# Adafruit_FONA_SIM5320_3G_Breakout.net
KiCad netlist of a schematic drawn in EAGLE
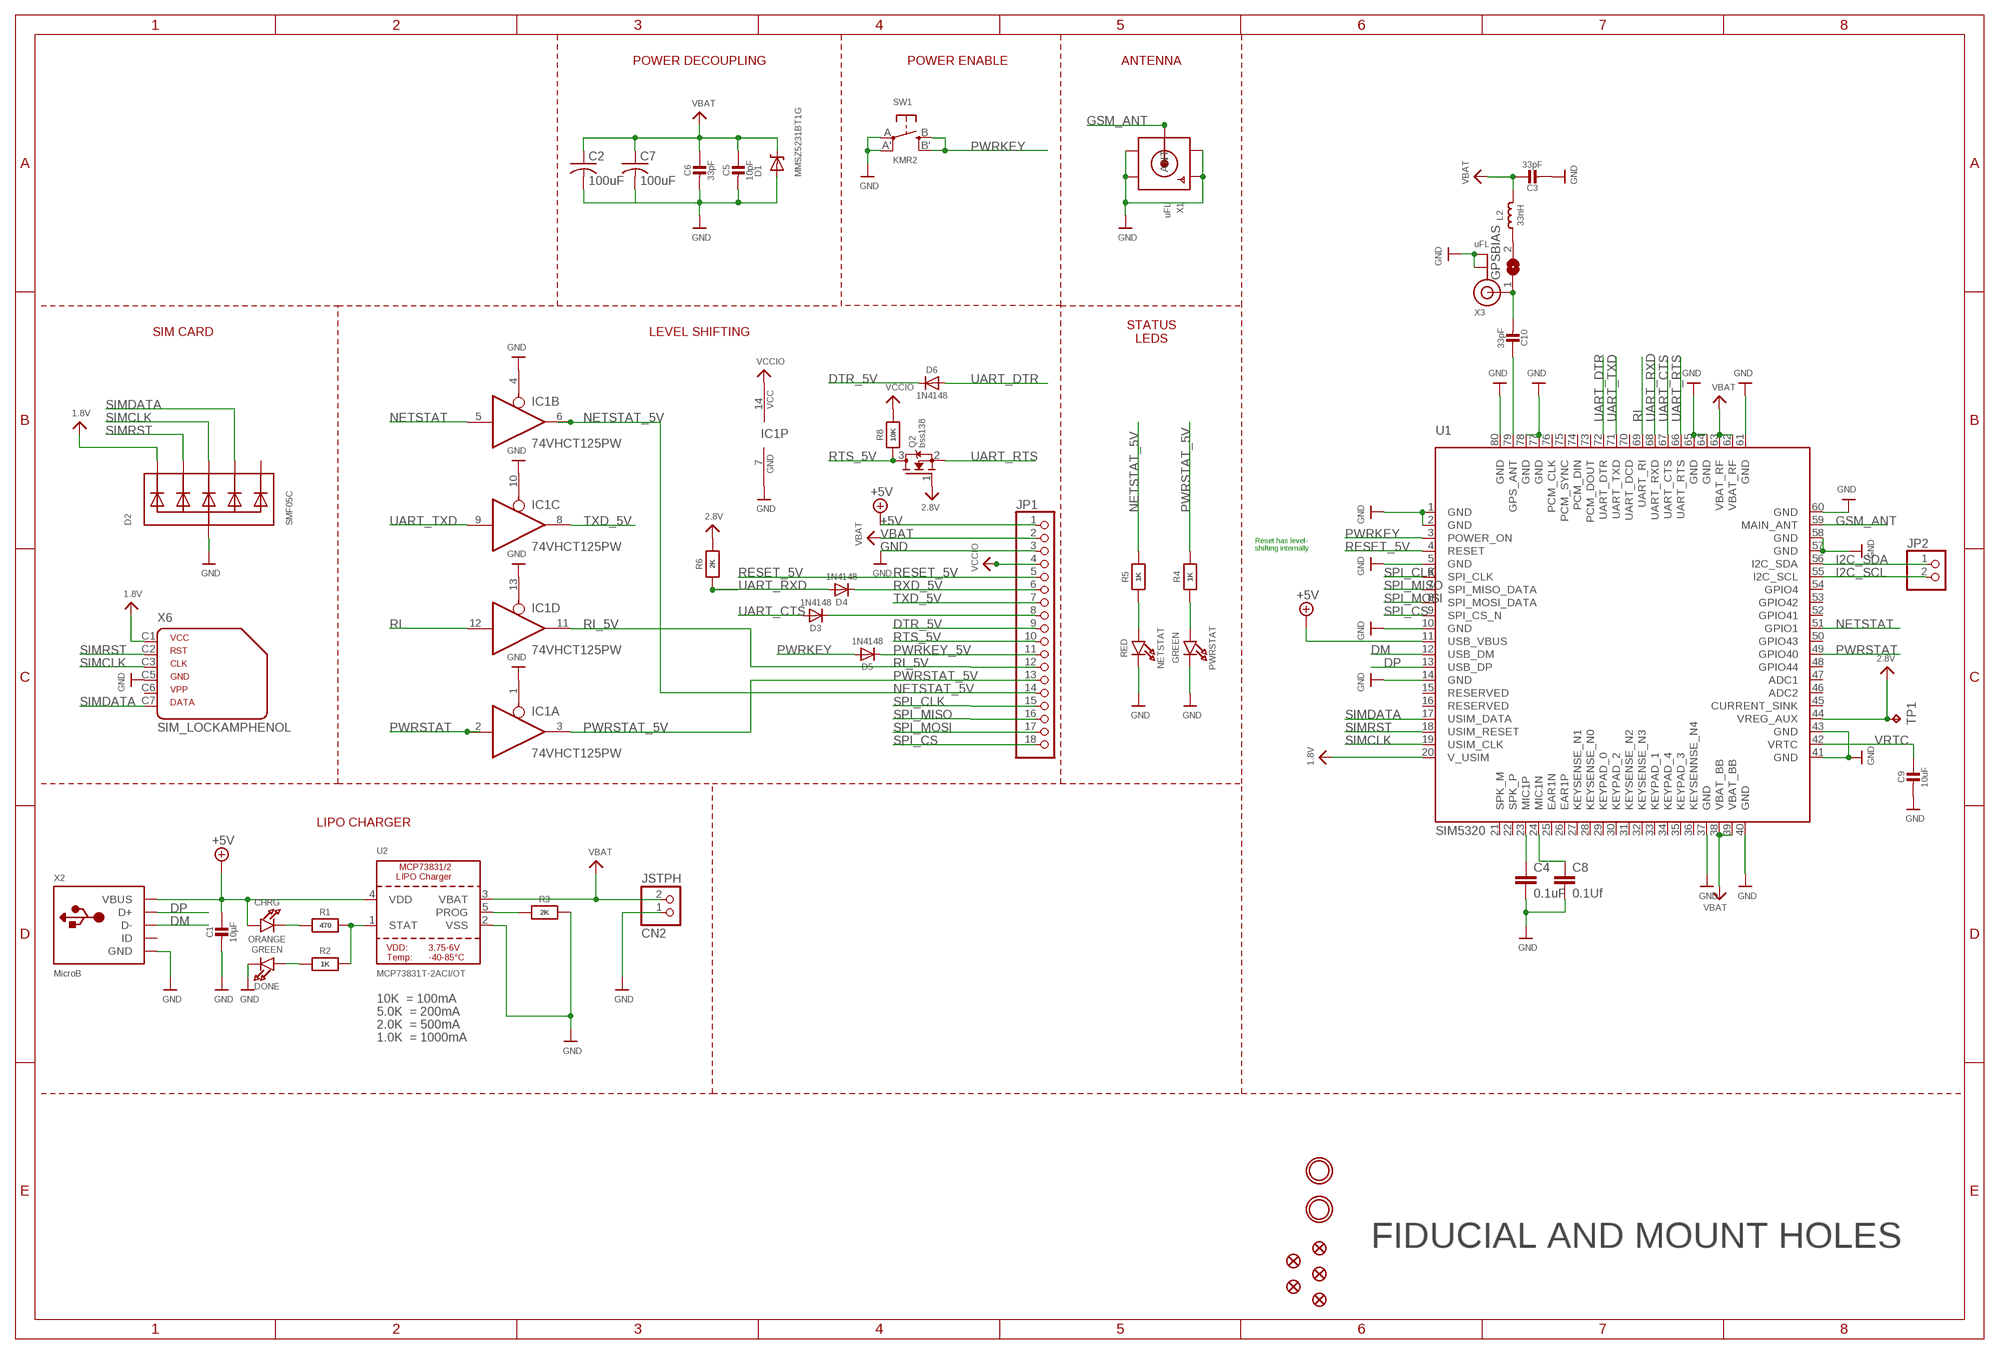
[diagram p0: schematic, sheet 1]

(export (version "E")
  (design (tool "Eeschema 10.0.6"))
  (components
    (comp (ref "C1")
      (value "10µF")
      (footprint "eagle-import:0805-NO")
      (libsource (lib "eagle-import") (part "CAP_CERAMIC0805-NOOUTLINE"))
    )
    (comp (ref "C2")
      (value "100uF")
      (footprint "eagle-import:C1210")
      (libsource (lib "eagle-import") (part "C-USC1210"))
    )
    (comp (ref "C3")
      (value "33pF")
      (footprint "eagle-import:0805-NO")
      (libsource (lib "eagle-import") (part "CAP_CERAMIC0805-NOOUTLINE"))
    )
    (comp (ref "C4")
      (value "0.1uF")
      (footprint "eagle-import:C1210")
      (libsource (lib "eagle-import") (part "C-EUC1210"))
    )
    (comp (ref "C5")
      (value "10pF")
      (footprint "eagle-import:0805-NO")
      (libsource (lib "eagle-import") (part "CAP_CERAMIC0805-NOOUTLINE"))
    )
    (comp (ref "C6")
      (value "33pF")
      (footprint "eagle-import:0805-NO")
      (libsource (lib "eagle-import") (part "CAP_CERAMIC0805-NOOUTLINE"))
    )
    (comp (ref "C7")
      (value "100uF")
      (footprint "eagle-import:C1210")
      (libsource (lib "eagle-import") (part "C-USC1210"))
    )
    (comp (ref "C8")
      (value "0.1Uf")
      (footprint "eagle-import:C1210")
      (libsource (lib "eagle-import") (part "C-EUC1210"))
    )
    (comp (ref "C9")
      (value "10uF")
      (footprint "eagle-import:0805-NO")
      (libsource (lib "eagle-import") (part "CAP_CERAMIC0805-NOOUTLINE"))
    )
    (comp (ref "C10")
      (value "33pF")
      (footprint "eagle-import:0805-NO")
      (libsource (lib "eagle-import") (part "CAP_CERAMIC0805-NOOUTLINE"))
    )
    (comp (ref "CHRG")
      (value "ORANGE")
      (footprint "eagle-import:CHIPLED_0805_NOOUTLINE")
      (libsource (lib "eagle-import") (part "LED0805_NOOUTLINE"))
    )
    (comp (ref "CN2")
      (value "JSTPH")
      (footprint "eagle-import:JSTPH2")
      (libsource (lib "eagle-import") (part "JST_2PIN"))
    )
    (comp (ref "D1")
      (value "MMSZ5231BT1G")
      (footprint "eagle-import:SOD-123")
      (libsource (lib "eagle-import") (part "DIODE-ZENERSOD123"))
    )
    (comp (ref "D2")
      (value "SMF05C")
      (footprint "eagle-import:SOT363")
      (libsource (lib "eagle-import") (part "TVSARRAY_5LANE"))
    )
    (comp (ref "D3")
      (value "1N4148")
      (footprint "eagle-import:SOD-323")
      (libsource (lib "eagle-import") (part "DIODESOD-323"))
    )
    (comp (ref "D4")
      (value "1N4148")
      (footprint "eagle-import:SOD-323")
      (libsource (lib "eagle-import") (part "DIODESOD-323"))
    )
    (comp (ref "D5")
      (value "1N4148")
      (footprint "eagle-import:SOD-323")
      (libsource (lib "eagle-import") (part "DIODESOD-323"))
    )
    (comp (ref "D6")
      (value "1N4148")
      (footprint "eagle-import:SOD-323")
      (libsource (lib "eagle-import") (part "DIODESOD-323"))
    )
    (comp (ref "DONE")
      (value "GREEN")
      (footprint "eagle-import:CHIPLED_0805_NOOUTLINE")
      (libsource (lib "eagle-import") (part "LED0805_NOOUTLINE"))
    )
    (comp (ref "FID1")
      (value "FIDUCIAL\"\"")
      (footprint "eagle-import:FIDUCIAL_1MM")
      (libsource (lib "eagle-import") (part "FIDUCIAL{dblquote}{dblquote}"))
    )
    (comp (ref "FID2")
      (value "FIDUCIAL\"\"")
      (footprint "eagle-import:FIDUCIAL_1MM")
      (libsource (lib "eagle-import") (part "FIDUCIAL{dblquote}{dblquote}"))
    )
    (comp (ref "FID3")
      (value "FIDUCIAL\"\"")
      (footprint "eagle-import:FIDUCIAL_1MM")
      (libsource (lib "eagle-import") (part "FIDUCIAL{dblquote}{dblquote}"))
    )
    (comp (ref "FID4")
      (value "FIDUCIAL\"\"")
      (footprint "eagle-import:FIDUCIAL_1MM")
      (libsource (lib "eagle-import") (part "FIDUCIAL{dblquote}{dblquote}"))
    )
    (comp (ref "FID5")
      (value "FIDUCIAL\"\"")
      (footprint "eagle-import:FIDUCIAL_1MM")
      (libsource (lib "eagle-import") (part "FIDUCIAL{dblquote}{dblquote}"))
    )
    (comp (ref "GPSBIAS")
      (value "SOLDERJUMPER")
      (footprint "eagle-import:SOLDERJUMPER_ARROW_NOPASTE")
      (libsource (lib "eagle-import") (part "SOLDERJUMPER"))
    )
    (comp (ref "IC1")
      (value "74VHCT125PW")
      (footprint "eagle-import:TSSOP14")
      (libsource (lib "eagle-import") (part "74125PWABT"))
    )
    (comp (ref "JP1")
      (value "HEADER-1X18")
      (footprint "eagle-import:1X18_ROUND70")
      (libsource (lib "eagle-import") (part "HEADER-1X18"))
    )
    (comp (ref "JP2")
      (value "HEADER-1X2ROUND")
      (footprint "eagle-import:1X02_ROUND")
      (libsource (lib "eagle-import") (part "HEADER-1X2ROUND"))
    )
    (comp (ref "L2")
      (value "33nH")
      (footprint "eagle-import:_0805MP")
      (libsource (lib "eagle-import") (part "INDUCTOR_0805MP"))
    )
    (comp (ref "NETSTAT")
      (value "RED")
      (footprint "eagle-import:CHIPLED_0805_NOOUTLINE")
      (libsource (lib "eagle-import") (part "LED0805_NOOUTLINE"))
    )
    (comp (ref "PWRSTAT")
      (value "GREEN")
      (footprint "eagle-import:CHIPLED_0805_NOOUTLINE")
      (libsource (lib "eagle-import") (part "LED0805_NOOUTLINE"))
    )
    (comp (ref "Q2")
      (value "bss138")
      (footprint "eagle-import:SOT23-WIDE")
      (libsource (lib "eagle-import") (part "MOSFET-NWIDE"))
    )
    (comp (ref "R1")
      (value "470")
      (footprint "eagle-import:0805-NO")
      (libsource (lib "eagle-import") (part "RESISTOR0805_NOOUTLINE"))
    )
    (comp (ref "R2")
      (value "1K")
      (footprint "eagle-import:0805-NO")
      (libsource (lib "eagle-import") (part "RESISTOR0805_NOOUTLINE"))
    )
    (comp (ref "R3")
      (value "2K")
      (footprint "eagle-import:0805-NO")
      (libsource (lib "eagle-import") (part "RESISTOR0805_NOOUTLINE"))
    )
    (comp (ref "R4")
      (value "1K")
      (footprint "eagle-import:0805-NO")
      (libsource (lib "eagle-import") (part "RESISTOR0805_NOOUTLINE"))
    )
    (comp (ref "R5")
      (value "1K")
      (footprint "eagle-import:0805-NO")
      (libsource (lib "eagle-import") (part "RESISTOR0805_NOOUTLINE"))
    )
    (comp (ref "R6")
      (value "2K")
      (footprint "eagle-import:0805-NO")
      (libsource (lib "eagle-import") (part "RESISTOR0805_NOOUTLINE"))
    )
    (comp (ref "R8")
      (value "10K")
      (footprint "eagle-import:0805-NO")
      (libsource (lib "eagle-import") (part "RESISTOR0805_NOOUTLINE"))
    )
    (comp (ref "SW1")
      (value "KMR2")
      (footprint "eagle-import:BTN_KMR2_4.6X2.8")
      (libsource (lib "eagle-import") (part "SWITCH_TACT_SMT4.6X2.8"))
    )
    (comp (ref "TP1")
      (value "TPTP11R")
      (footprint "eagle-import:TP11R")
      (libsource (lib "eagle-import") (part "TPTP11R"))
    )
    (comp (ref "U$33")
      (value "MOUNTINGHOLE2.5")
      (footprint "eagle-import:MOUNTINGHOLE_2.5_PLATED")
      (libsource (lib "eagle-import") (part "MOUNTINGHOLE2.5"))
    )
    (comp (ref "U$34")
      (value "MOUNTINGHOLE2.5")
      (footprint "eagle-import:MOUNTINGHOLE_2.5_PLATED")
      (libsource (lib "eagle-import") (part "MOUNTINGHOLE2.5"))
    )
    (comp (ref "U1")
      (value "SIM5320")
      (footprint "eagle-import:SIM5320")
      (libsource (lib "eagle-import") (part "GSM_SIM5320_LITERAL"))
    )
    (comp (ref "U2")
      (value "MCP73831T-2ACI/OT")
      (footprint "eagle-import:SOT23-5")
      (libsource (lib "eagle-import") (part "MCP73831/2"))
    )
    (comp (ref "X1")
      (value "uFL")
      (footprint "eagle-import:SMA_EDGELAUNCH_UFL")
      (libsource (lib "eagle-import") (part "SMACONNECTOR_EDGE_UFL"))
    )
    (comp (ref "X2")
      (value "MicroB")
      (footprint "eagle-import:4UCONN_20329")
      (libsource (lib "eagle-import") (part "USBMICRO_20329"))
    )
    (comp (ref "X3")
      (value "uFL")
      (footprint "eagle-import:U.FL")
      (libsource (lib "eagle-import") (part "ANTENNA_U.FL"))
    )
    (comp (ref "X6")
      (value "SIM_LOCKAMPHENOL")
      (footprint "eagle-import:C707_10M006_512_2")
      (libsource (lib "eagle-import") (part "SIM_LOCKAMPHENOL"))
    )
  )
  (nets
    (net (code "1") (name "+5V") (class "Default")
      (node (ref "C1") (pin "1") (pinfunction "1_1") (pintype "passive"))
      (node (ref "CHRG") (pin "A") (pinfunction "A_A") (pintype "passive"))
      (node (ref "JP1") (pin "1") (pinfunction "1_1") (pintype "passive"))
      (node (ref "U1") (pin "11") (pinfunction "USB_VBUS_11") (pintype "bidirectional"))
      (node (ref "U2") (pin "4") (pinfunction "VDD_4") (pintype "power_in"))
      (node (ref "X2") (pin "VBUS") (pinfunction "VBUS_VBUS") (pintype "power_in"))
    )
    (net (code "2") (name "/DM") (class "Default")
      (node (ref "U1") (pin "12") (pinfunction "USB_DM_12") (pintype "bidirectional"))
      (node (ref "X2") (pin "D-") (pinfunction "D-_D-") (pintype "bidirectional"))
    )
    (net (code "3") (name "/DP") (class "Default")
      (node (ref "U1") (pin "13") (pinfunction "USB_DP_13") (pintype "bidirectional"))
      (node (ref "X2") (pin "D+") (pinfunction "D+_D+") (pintype "bidirectional"))
    )
    (net (code "4") (name "/DTR_5V") (class "Default")
      (node (ref "D6") (pin "C") (pinfunction "C_C") (pintype "passive"))
      (node (ref "JP1") (pin "9") (pinfunction "9_9") (pintype "passive"))
    )
    (net (code "5") (name "/GSM_ANT") (class "Default")
      (node (ref "U1") (pin "59") (pinfunction "MAIN_ANT_59") (pintype "bidirectional"))
      (node (ref "X1") (pin "P") (pinfunction "ANT_P") (pintype "bidirectional"))
    )
    (net (code "6") (name "/I2C_SCL") (class "Default")
      (node (ref "JP2") (pin "2") (pinfunction "2_2") (pintype "passive"))
      (node (ref "U1") (pin "55") (pinfunction "I2C_SCL_55") (pintype "bidirectional"))
    )
    (net (code "7") (name "/I2C_SDA") (class "Default")
      (node (ref "JP2") (pin "1") (pinfunction "1_1") (pintype "passive"))
      (node (ref "U1") (pin "56") (pinfunction "I2C_SDA_56") (pintype "bidirectional"))
    )
    (net (code "8") (name "/NETSTAT") (class "Default")
      (node (ref "IC1") (pin "5") (pinfunction "I_5") (pintype "input"))
      (node (ref "U1") (pin "51") (pinfunction "GPIO1_51") (pintype "bidirectional"))
    )
    (net (code "9") (name "/NETSTAT_5V") (class "Default")
      (node (ref "IC1") (pin "6") (pinfunction "O_6") (pintype "tri_state"))
      (node (ref "JP1") (pin "14") (pinfunction "14_14") (pintype "passive"))
      (node (ref "R5") (pin "2") (pinfunction "2_2") (pintype "passive"))
    )
    (net (code "10") (name "/PWRKEY") (class "Default")
      (node (ref "D5") (pin "A") (pinfunction "A_A") (pintype "passive"))
      (node (ref "SW1") (pin "B") (pinfunction "S_B") (pintype "passive"))
      (node (ref "SW1") (pin "B'") (pinfunction "S1_B'") (pintype "passive"))
      (node (ref "U1") (pin "3") (pinfunction "POWER_ON_3") (pintype "bidirectional"))
    )
    (net (code "11") (name "/PWRKEY_5V") (class "Default")
      (node (ref "D5") (pin "C") (pinfunction "C_C") (pintype "passive"))
      (node (ref "JP1") (pin "11") (pinfunction "11_11") (pintype "passive"))
    )
    (net (code "12") (name "/PWRSTAT") (class "Default")
      (node (ref "IC1") (pin "2") (pinfunction "I_2") (pintype "input"))
      (node (ref "U1") (pin "49") (pinfunction "GPIO40_49") (pintype "bidirectional"))
    )
    (net (code "13") (name "/PWRSTAT_5V") (class "Default")
      (node (ref "IC1") (pin "3") (pinfunction "O_3") (pintype "tri_state"))
      (node (ref "JP1") (pin "13") (pinfunction "13_13") (pintype "passive"))
      (node (ref "R4") (pin "2") (pinfunction "2_2") (pintype "passive"))
    )
    (net (code "14") (name "/RESET_5V") (class "Default")
      (node (ref "JP1") (pin "5") (pinfunction "5_5") (pintype "passive"))
      (node (ref "U1") (pin "4") (pinfunction "RESET_4") (pintype "bidirectional"))
    )
    (net (code "15") (name "/RI") (class "Default")
      (node (ref "IC1") (pin "12") (pinfunction "I_12") (pintype "input"))
      (node (ref "U1") (pin "69") (pinfunction "UART_RI_69") (pintype "bidirectional"))
    )
    (net (code "16") (name "/RI_5V") (class "Default")
      (node (ref "IC1") (pin "11") (pinfunction "O_11") (pintype "tri_state"))
      (node (ref "JP1") (pin "12") (pinfunction "12_12") (pintype "passive"))
    )
    (net (code "17") (name "/RTS_5V") (class "Default")
      (node (ref "JP1") (pin "10") (pinfunction "10_10") (pintype "passive"))
      (node (ref "Q2") (pin "3") (pinfunction "D_3") (pintype "bidirectional"))
      (node (ref "R8") (pin "1") (pinfunction "1_1") (pintype "passive"))
    )
    (net (code "18") (name "/RXD_5V") (class "Default")
      (node (ref "D4") (pin "C") (pinfunction "C_C") (pintype "passive"))
      (node (ref "JP1") (pin "6") (pinfunction "6_6") (pintype "passive"))
    )
    (net (code "19") (name "/SIMCLK") (class "Default")
      (node (ref "D2") (pin "4") (pinfunction "C3_4") (pintype "passive"))
      (node (ref "U1") (pin "19") (pinfunction "USIM_CLK_19") (pintype "bidirectional"))
      (node (ref "X6") (pin "C3") (pinfunction "3_C3") (pintype "passive"))
    )
    (net (code "20") (name "/SIMDATA") (class "Default")
      (node (ref "D2") (pin "5") (pinfunction "C4_5") (pintype "passive"))
      (node (ref "U1") (pin "17") (pinfunction "USIM_DATA_17") (pintype "bidirectional"))
      (node (ref "X6") (pin "C7") (pinfunction "6_C7") (pintype "passive"))
    )
    (net (code "21") (name "/SIMRST") (class "Default")
      (node (ref "D2") (pin "3") (pinfunction "C2_3") (pintype "passive"))
      (node (ref "U1") (pin "18") (pinfunction "USIM_RESET_18") (pintype "bidirectional"))
      (node (ref "X6") (pin "C2") (pinfunction "2_C2") (pintype "passive"))
    )
    (net (code "22") (name "/SPI_CLK") (class "Default")
      (node (ref "JP1") (pin "15") (pinfunction "15_15") (pintype "passive"))
      (node (ref "U1") (pin "6") (pinfunction "SPI_CLK_6") (pintype "bidirectional"))
    )
    (net (code "23") (name "/SPI_CS") (class "Default")
      (node (ref "JP1") (pin "18") (pinfunction "18_18") (pintype "passive"))
      (node (ref "U1") (pin "9") (pinfunction "SPI_CS_N_9") (pintype "bidirectional"))
    )
    (net (code "24") (name "/SPI_MISO") (class "Default")
      (node (ref "JP1") (pin "16") (pinfunction "16_16") (pintype "passive"))
      (node (ref "U1") (pin "7") (pinfunction "SPI_MISO_DATA_7") (pintype "bidirectional"))
    )
    (net (code "25") (name "/SPI_MOSI") (class "Default")
      (node (ref "JP1") (pin "17") (pinfunction "17_17") (pintype "passive"))
      (node (ref "U1") (pin "8") (pinfunction "SPI_MOSI_DATA_8") (pintype "bidirectional"))
    )
    (net (code "26") (name "/TXD_5V") (class "Default")
      (node (ref "IC1") (pin "8") (pinfunction "O_8") (pintype "tri_state"))
      (node (ref "JP1") (pin "7") (pinfunction "7_7") (pintype "passive"))
    )
    (net (code "27") (name "/UART_CTS") (class "Default")
      (node (ref "D3") (pin "A") (pinfunction "A_A") (pintype "passive"))
      (node (ref "U1") (pin "67") (pinfunction "UART_CTS_67") (pintype "bidirectional"))
    )
    (net (code "28") (name "/UART_DTR") (class "Default")
      (node (ref "D6") (pin "A") (pinfunction "A_A") (pintype "passive"))
      (node (ref "U1") (pin "72") (pinfunction "UART_DTR_72") (pintype "bidirectional"))
    )
    (net (code "29") (name "/UART_RTS") (class "Default")
      (node (ref "Q2") (pin "2") (pinfunction "S_2") (pintype "bidirectional"))
      (node (ref "U1") (pin "66") (pinfunction "UART_RTS_66") (pintype "bidirectional"))
    )
    (net (code "30") (name "/UART_RXD") (class "Default")
      (node (ref "D4") (pin "A") (pinfunction "A_A") (pintype "passive"))
      (node (ref "R6") (pin "1") (pinfunction "1_1") (pintype "passive"))
      (node (ref "U1") (pin "68") (pinfunction "UART_RXD_68") (pintype "bidirectional"))
    )
    (net (code "31") (name "/UART_TXD") (class "Default")
      (node (ref "IC1") (pin "9") (pinfunction "I_9") (pintype "input"))
      (node (ref "U1") (pin "71") (pinfunction "UART_TXD_71") (pintype "bidirectional"))
    )
    (net (code "32") (name "/VRTC") (class "Default")
      (node (ref "C9") (pin "1") (pinfunction "1_1") (pintype "passive"))
      (node (ref "U1") (pin "42") (pinfunction "VRTC_42") (pintype "bidirectional"))
    )
    (net (code "33") (name "1.8V") (class "Default")
      (node (ref "D2") (pin "1") (pinfunction "C1_1") (pintype "passive"))
      (node (ref "U1") (pin "20") (pinfunction "V_USIM_20") (pintype "bidirectional"))
      (node (ref "X6") (pin "C1") (pinfunction "1_C1") (pintype "passive"))
    )
    (net (code "34") (name "2.8V") (class "Default")
      (node (ref "Q2") (pin "1") (pinfunction "G_1") (pintype "bidirectional"))
      (node (ref "R6") (pin "2") (pinfunction "2_2") (pintype "passive"))
      (node (ref "TP1") (pin "TP") (pinfunction "TP_TP") (pintype "input"))
      (node (ref "U1") (pin "44") (pinfunction "VREG_AUX_44") (pintype "bidirectional"))
    )
    (net (code "35") (name "GND") (class "Default")
      (node (ref "C1") (pin "2") (pinfunction "2_2") (pintype "passive"))
      (node (ref "C2") (pin "2") (pinfunction "2_2") (pintype "passive"))
      (node (ref "C3") (pin "2") (pinfunction "2_2") (pintype "passive"))
      (node (ref "C4") (pin "2") (pinfunction "2_2") (pintype "passive"))
      (node (ref "C5") (pin "2") (pinfunction "2_2") (pintype "passive"))
      (node (ref "C6") (pin "2") (pinfunction "2_2") (pintype "passive"))
      (node (ref "C7") (pin "2") (pinfunction "2_2") (pintype "passive"))
      (node (ref "C8") (pin "2") (pinfunction "2_2") (pintype "passive"))
      (node (ref "C9") (pin "2") (pinfunction "2_2") (pintype "passive"))
      (node (ref "CN2") (pin "1") (pinfunction "1_1") (pintype "passive"))
      (node (ref "D1") (pin "A") (pinfunction "A_A") (pintype "passive"))
      (node (ref "D2") (pin "2") (pinfunction "A_2") (pintype "passive"))
      (node (ref "DONE") (pin "C") (pinfunction "C_C") (pintype "passive"))
      (node (ref "IC1") (pin "1") (pinfunction "OE_1") (pintype "input"))
      (node (ref "IC1") (pin "10") (pinfunction "OE_10") (pintype "input"))
      (node (ref "IC1") (pin "13") (pinfunction "OE_13") (pintype "input"))
      (node (ref "IC1") (pin "4") (pinfunction "OE_4") (pintype "input"))
      (node (ref "IC1") (pin "7") (pinfunction "GND_7") (pintype "power_in"))
      (node (ref "JP1") (pin "3") (pinfunction "3_3") (pintype "passive"))
      (node (ref "NETSTAT") (pin "C") (pinfunction "C_C") (pintype "passive"))
      (node (ref "PWRSTAT") (pin "C") (pinfunction "C_C") (pintype "passive"))
      (node (ref "R3") (pin "2") (pinfunction "2_2") (pintype "passive"))
      (node (ref "SW1") (pin "A") (pinfunction "P_A") (pintype "passive"))
      (node (ref "SW1") (pin "A'") (pinfunction "P1_A'") (pintype "passive"))
      (node (ref "U1") (pin "1") (pinfunction "GND_1") (pintype "bidirectional"))
      (node (ref "U1") (pin "10") (pinfunction "GND_10") (pintype "bidirectional"))
      (node (ref "U1") (pin "14") (pinfunction "GND_14") (pintype "bidirectional"))
      (node (ref "U1") (pin "2") (pinfunction "GND_2") (pintype "bidirectional"))
      (node (ref "U1") (pin "37") (pinfunction "GND_37") (pintype "bidirectional"))
      (node (ref "U1") (pin "40") (pinfunction "GND_40") (pintype "bidirectional"))
      (node (ref "U1") (pin "41") (pinfunction "GND_41") (pintype "bidirectional"))
      (node (ref "U1") (pin "43") (pinfunction "GND_43") (pintype "bidirectional"))
      (node (ref "U1") (pin "5") (pinfunction "GND_5") (pintype "bidirectional"))
      (node (ref "U1") (pin "57") (pinfunction "GND_57") (pintype "bidirectional"))
      (node (ref "U1") (pin "58") (pinfunction "GND_58") (pintype "bidirectional"))
      (node (ref "U1") (pin "60") (pinfunction "GND_60") (pintype "bidirectional"))
      (node (ref "U1") (pin "61") (pinfunction "GND_61") (pintype "bidirectional"))
      (node (ref "U1") (pin "64") (pinfunction "GND_64") (pintype "bidirectional"))
      (node (ref "U1") (pin "65") (pinfunction "GND_65") (pintype "bidirectional"))
      (node (ref "U1") (pin "77") (pinfunction "GND_77") (pintype "bidirectional"))
      (node (ref "U1") (pin "78") (pinfunction "GND_78") (pintype "bidirectional"))
      (node (ref "U1") (pin "80") (pinfunction "GND_80") (pintype "bidirectional"))
      (node (ref "U2") (pin "2") (pinfunction "VSS_2") (pintype "power_in"))
      (node (ref "X1") (pin "GND@1") (pinfunction "GND1_GND@1") (pintype "power_in"))
      (node (ref "X1") (pin "GND@2") (pinfunction "GND2_GND@2") (pintype "power_in"))
      (node (ref "X1") (pin "GND@3") (pinfunction "GND3_GND@3") (pintype "power_in"))
      (node (ref "X1") (pin "GND@4") (pinfunction "GND4_GND@4") (pintype "power_in"))
      (node (ref "X2") (pin "BASE@1") (pinfunction "GND_BASE@1") (pintype "power_in"))
      (node (ref "X2") (pin "BASE@2") (pinfunction "GND_BASE@2") (pintype "power_in"))
      (node (ref "X2") (pin "GND") (pinfunction "GND_GND") (pintype "power_in"))
      (node (ref "X2") (pin "SPRT@1") (pinfunction "GND_SPRT@1") (pintype "power_in"))
      (node (ref "X2") (pin "SPRT@2") (pinfunction "GND_SPRT@2") (pintype "power_in"))
      (node (ref "X2") (pin "SPRT@3") (pinfunction "GND_SPRT@3") (pintype "power_in"))
      (node (ref "X2") (pin "SPRT@4") (pinfunction "GND_SPRT@4") (pintype "power_in"))
      (node (ref "X3") (pin "1") (pinfunction "GND_1") (pintype "passive"))
      (node (ref "X3") (pin "2") (pinfunction "GND_2") (pintype "passive"))
      (node (ref "X6") (pin "C5") (pinfunction "4_C5") (pintype "passive"))
    )
    (net (code "36") (name "Net-(CHRG-PadC)") (class "Default")
      (node (ref "CHRG") (pin "C") (pinfunction "C_C") (pintype "passive"))
      (node (ref "R1") (pin "1") (pinfunction "1_1") (pintype "passive"))
    )
    (net (code "37") (name "Net-(D3-PadC)") (class "Default")
      (node (ref "D3") (pin "C") (pinfunction "C_C") (pintype "passive"))
      (node (ref "JP1") (pin "8") (pinfunction "8_8") (pintype "passive"))
    )
    (net (code "38") (name "Net-(DONE-PadA)") (class "Default")
      (node (ref "DONE") (pin "A") (pinfunction "A_A") (pintype "passive"))
      (node (ref "R2") (pin "1") (pinfunction "1_1") (pintype "passive"))
    )
    (net (code "39") (name "Net-(GPSBIAS-Pad2)") (class "Default")
      (node (ref "GPSBIAS") (pin "2") (pinfunction "2_2") (pintype "passive"))
      (node (ref "L2") (pin "1") (pinfunction "1_1") (pintype "passive"))
    )
    (net (code "40") (name "Net-(NETSTAT-PadA)") (class "Default")
      (node (ref "NETSTAT") (pin "A") (pinfunction "A_A") (pintype "passive"))
      (node (ref "R5") (pin "1") (pinfunction "1_1") (pintype "passive"))
    )
    (net (code "41") (name "Net-(PWRSTAT-PadA)") (class "Default")
      (node (ref "PWRSTAT") (pin "A") (pinfunction "A_A") (pintype "passive"))
      (node (ref "R4") (pin "1") (pinfunction "1_1") (pintype "passive"))
    )
    (net (code "42") (name "Net-(U1-GPS_ANT)") (class "Default")
      (node (ref "C10") (pin "1") (pinfunction "1_1") (pintype "passive"))
      (node (ref "U1") (pin "79") (pinfunction "GPS_ANT_79") (pintype "bidirectional"))
    )
    (net (code "43") (name "Net-(U1-MIC1N)") (class "Default")
      (node (ref "C8") (pin "1") (pinfunction "1_1") (pintype "passive"))
      (node (ref "U1") (pin "24") (pinfunction "MIC1N_24") (pintype "bidirectional"))
    )
    (net (code "44") (name "Net-(U1-MIC1P)") (class "Default")
      (node (ref "C4") (pin "1") (pinfunction "1_1") (pintype "passive"))
      (node (ref "U1") (pin "23") (pinfunction "MIC1P_23") (pintype "bidirectional"))
    )
    (net (code "45") (name "Net-(U2-PROG)") (class "Default")
      (node (ref "R3") (pin "1") (pinfunction "1_1") (pintype "passive"))
      (node (ref "U2") (pin "5") (pinfunction "PROG_5") (pintype "input"))
    )
    (net (code "46") (name "Net-(U2-STAT)") (class "Default")
      (node (ref "R1") (pin "2") (pinfunction "2_2") (pintype "passive"))
      (node (ref "R2") (pin "2") (pinfunction "2_2") (pintype "passive"))
      (node (ref "U2") (pin "1") (pinfunction "STAT_1") (pintype "output"))
    )
    (net (code "47") (name "Net-(X3-SIGNAL)") (class "Default")
      (node (ref "C10") (pin "2") (pinfunction "2_2") (pintype "passive"))
      (node (ref "GPSBIAS") (pin "1") (pinfunction "1_1") (pintype "passive"))
      (node (ref "X3") (pin "3") (pinfunction "SIGNAL_3") (pintype "passive"))
    )
    (net (code "48") (name "VBAT") (class "Default")
      (node (ref "C2") (pin "1") (pinfunction "1_1") (pintype "passive"))
      (node (ref "C3") (pin "1") (pinfunction "1_1") (pintype "passive"))
      (node (ref "C5") (pin "1") (pinfunction "1_1") (pintype "passive"))
      (node (ref "C6") (pin "1") (pinfunction "1_1") (pintype "passive"))
      (node (ref "C7") (pin "1") (pinfunction "1_1") (pintype "passive"))
      (node (ref "CN2") (pin "2") (pinfunction "2_2") (pintype "passive"))
      (node (ref "D1") (pin "C") (pinfunction "C_C") (pintype "passive"))
      (node (ref "JP1") (pin "2") (pinfunction "2_2") (pintype "passive"))
      (node (ref "L2") (pin "2") (pinfunction "2_2") (pintype "passive"))
      (node (ref "U1") (pin "38") (pinfunction "VBAT_BB_38") (pintype "bidirectional"))
      (node (ref "U1") (pin "39") (pinfunction "VBAT_BB_39") (pintype "bidirectional"))
      (node (ref "U1") (pin "62") (pinfunction "VBAT_RF_62") (pintype "bidirectional"))
      (node (ref "U1") (pin "63") (pinfunction "VBAT_RF_63") (pintype "bidirectional"))
      (node (ref "U2") (pin "3") (pinfunction "VBAT_3") (pintype "power_in"))
    )
    (net (code "49") (name "VCCIO") (class "Default")
      (node (ref "IC1") (pin "14") (pinfunction "VCC_14") (pintype "power_in"))
      (node (ref "JP1") (pin "4") (pinfunction "4_4") (pintype "passive"))
      (node (ref "R8") (pin "2") (pinfunction "2_2") (pintype "passive"))
    )
    (net (code "50") (name "unconnected-(D2-C5-Pad6)") (class "Default")
      (node (ref "D2") (pin "6") (pinfunction "C5_6") (pintype "passive"))
    )
    (net (code "51") (name "unconnected-(U1-ADC1-Pad47)") (class "Default")
      (node (ref "U1") (pin "47") (pinfunction "ADC1_47") (pintype "bidirectional"))
    )
    (net (code "52") (name "unconnected-(U1-ADC2-Pad46)") (class "Default")
      (node (ref "U1") (pin "46") (pinfunction "ADC2_46") (pintype "bidirectional"))
    )
    (net (code "53") (name "unconnected-(U1-CURRENT_SINK-Pad45)") (class "Default")
      (node (ref "U1") (pin "45") (pinfunction "CURRENT_SINK_45") (pintype "bidirectional"))
    )
    (net (code "54") (name "unconnected-(U1-EAR1N-Pad25)") (class "Default")
      (node (ref "U1") (pin "25") (pinfunction "EAR1N_25") (pintype "bidirectional"))
    )
    (net (code "55") (name "unconnected-(U1-EAR1P-Pad26)") (class "Default")
      (node (ref "U1") (pin "26") (pinfunction "EAR1P_26") (pintype "bidirectional"))
    )
    (net (code "56") (name "unconnected-(U1-GPIO4-Pad54)") (class "Default")
      (node (ref "U1") (pin "54") (pinfunction "GPIO4_54") (pintype "bidirectional"))
    )
    (net (code "57") (name "unconnected-(U1-GPIO41-Pad52)") (class "Default")
      (node (ref "U1") (pin "52") (pinfunction "GPIO41_52") (pintype "bidirectional"))
    )
    (net (code "58") (name "unconnected-(U1-GPIO42-Pad53)") (class "Default")
      (node (ref "U1") (pin "53") (pinfunction "GPIO42_53") (pintype "bidirectional"))
    )
    (net (code "59") (name "unconnected-(U1-GPIO43-Pad50)") (class "Default")
      (node (ref "U1") (pin "50") (pinfunction "GPIO43_50") (pintype "bidirectional"))
    )
    (net (code "60") (name "unconnected-(U1-GPIO44-Pad48)") (class "Default")
      (node (ref "U1") (pin "48") (pinfunction "GPIO44_48") (pintype "bidirectional"))
    )
    (net (code "61") (name "unconnected-(U1-KEYPAD_0-Pad29)") (class "Default")
      (node (ref "U1") (pin "29") (pinfunction "KEYPAD_0_29") (pintype "bidirectional"))
    )
    (net (code "62") (name "unconnected-(U1-KEYPAD_1-Pad33)") (class "Default")
      (node (ref "U1") (pin "33") (pinfunction "KEYPAD_1_33") (pintype "bidirectional"))
    )
    (net (code "63") (name "unconnected-(U1-KEYPAD_2-Pad30)") (class "Default")
      (node (ref "U1") (pin "30") (pinfunction "KEYPAD_2_30") (pintype "bidirectional"))
    )
    (net (code "64") (name "unconnected-(U1-KEYPAD_3-Pad35)") (class "Default")
      (node (ref "U1") (pin "35") (pinfunction "KEYPAD_3_35") (pintype "bidirectional"))
    )
    (net (code "65") (name "unconnected-(U1-KEYPAD_4-Pad34)") (class "Default")
      (node (ref "U1") (pin "34") (pinfunction "KEYPAD_4_34") (pintype "bidirectional"))
    )
    (net (code "66") (name "unconnected-(U1-KEYSENNSE_N4-Pad36)") (class "Default")
      (node (ref "U1") (pin "36") (pinfunction "KEYSENNSE_N4_36") (pintype "bidirectional"))
    )
    (net (code "67") (name "unconnected-(U1-KEYSENSE_N0-Pad28)") (class "Default")
      (node (ref "U1") (pin "28") (pinfunction "KEYSENSE_N0_28") (pintype "bidirectional"))
    )
    (net (code "68") (name "unconnected-(U1-KEYSENSE_N1-Pad27)") (class "Default")
      (node (ref "U1") (pin "27") (pinfunction "KEYSENSE_N1_27") (pintype "bidirectional"))
    )
    (net (code "69") (name "unconnected-(U1-KEYSENSE_N2-Pad31)") (class "Default")
      (node (ref "U1") (pin "31") (pinfunction "KEYSENSE_N2_31") (pintype "bidirectional"))
    )
    (net (code "70") (name "unconnected-(U1-KEYSENSE_N3-Pad32)") (class "Default")
      (node (ref "U1") (pin "32") (pinfunction "KEYSENSE_N3_32") (pintype "bidirectional"))
    )
    (net (code "71") (name "unconnected-(U1-PCM_CLK-Pad76)") (class "Default")
      (node (ref "U1") (pin "76") (pinfunction "PCM_CLK_76") (pintype "bidirectional"))
    )
    (net (code "72") (name "unconnected-(U1-PCM_DIN-Pad74)") (class "Default")
      (node (ref "U1") (pin "74") (pinfunction "PCM_DIN_74") (pintype "bidirectional"))
    )
    (net (code "73") (name "unconnected-(U1-PCM_DOUT-Pad73)") (class "Default")
      (node (ref "U1") (pin "73") (pinfunction "PCM_DOUT_73") (pintype "bidirectional"))
    )
    (net (code "74") (name "unconnected-(U1-PCM_SYNC-Pad75)") (class "Default")
      (node (ref "U1") (pin "75") (pinfunction "PCM_SYNC_75") (pintype "bidirectional"))
    )
    (net (code "75") (name "unconnected-(U1-RESERVED-Pad15)") (class "Default")
      (node (ref "U1") (pin "15") (pinfunction "RESERVED_15") (pintype "bidirectional"))
    )
    (net (code "76") (name "unconnected-(U1-RESERVED-Pad16)") (class "Default")
      (node (ref "U1") (pin "16") (pinfunction "RESERVED_16") (pintype "bidirectional"))
    )
    (net (code "77") (name "unconnected-(U1-SPK_M-Pad21)") (class "Default")
      (node (ref "U1") (pin "21") (pinfunction "SPK_M_21") (pintype "bidirectional"))
    )
    (net (code "78") (name "unconnected-(U1-SPK_P-Pad22)") (class "Default")
      (node (ref "U1") (pin "22") (pinfunction "SPK_P_22") (pintype "bidirectional"))
    )
    (net (code "79") (name "unconnected-(U1-UART_DCD-Pad70)") (class "Default")
      (node (ref "U1") (pin "70") (pinfunction "UART_DCD_70") (pintype "bidirectional"))
    )
    (net (code "80") (name "unconnected-(X2-PadID)") (class "Default")
      (node (ref "X2") (pin "ID") (pinfunction "ID_ID") (pintype "bidirectional"))
    )
    (net (code "81") (name "unconnected-(X6-5-PadC6)") (class "Default")
      (node (ref "X6") (pin "C6") (pinfunction "5_C6") (pintype "passive"))
    )
  )
)
